# ESP32_Dongle.net
KiCad netlist of a schematic drawn in Altium Designer
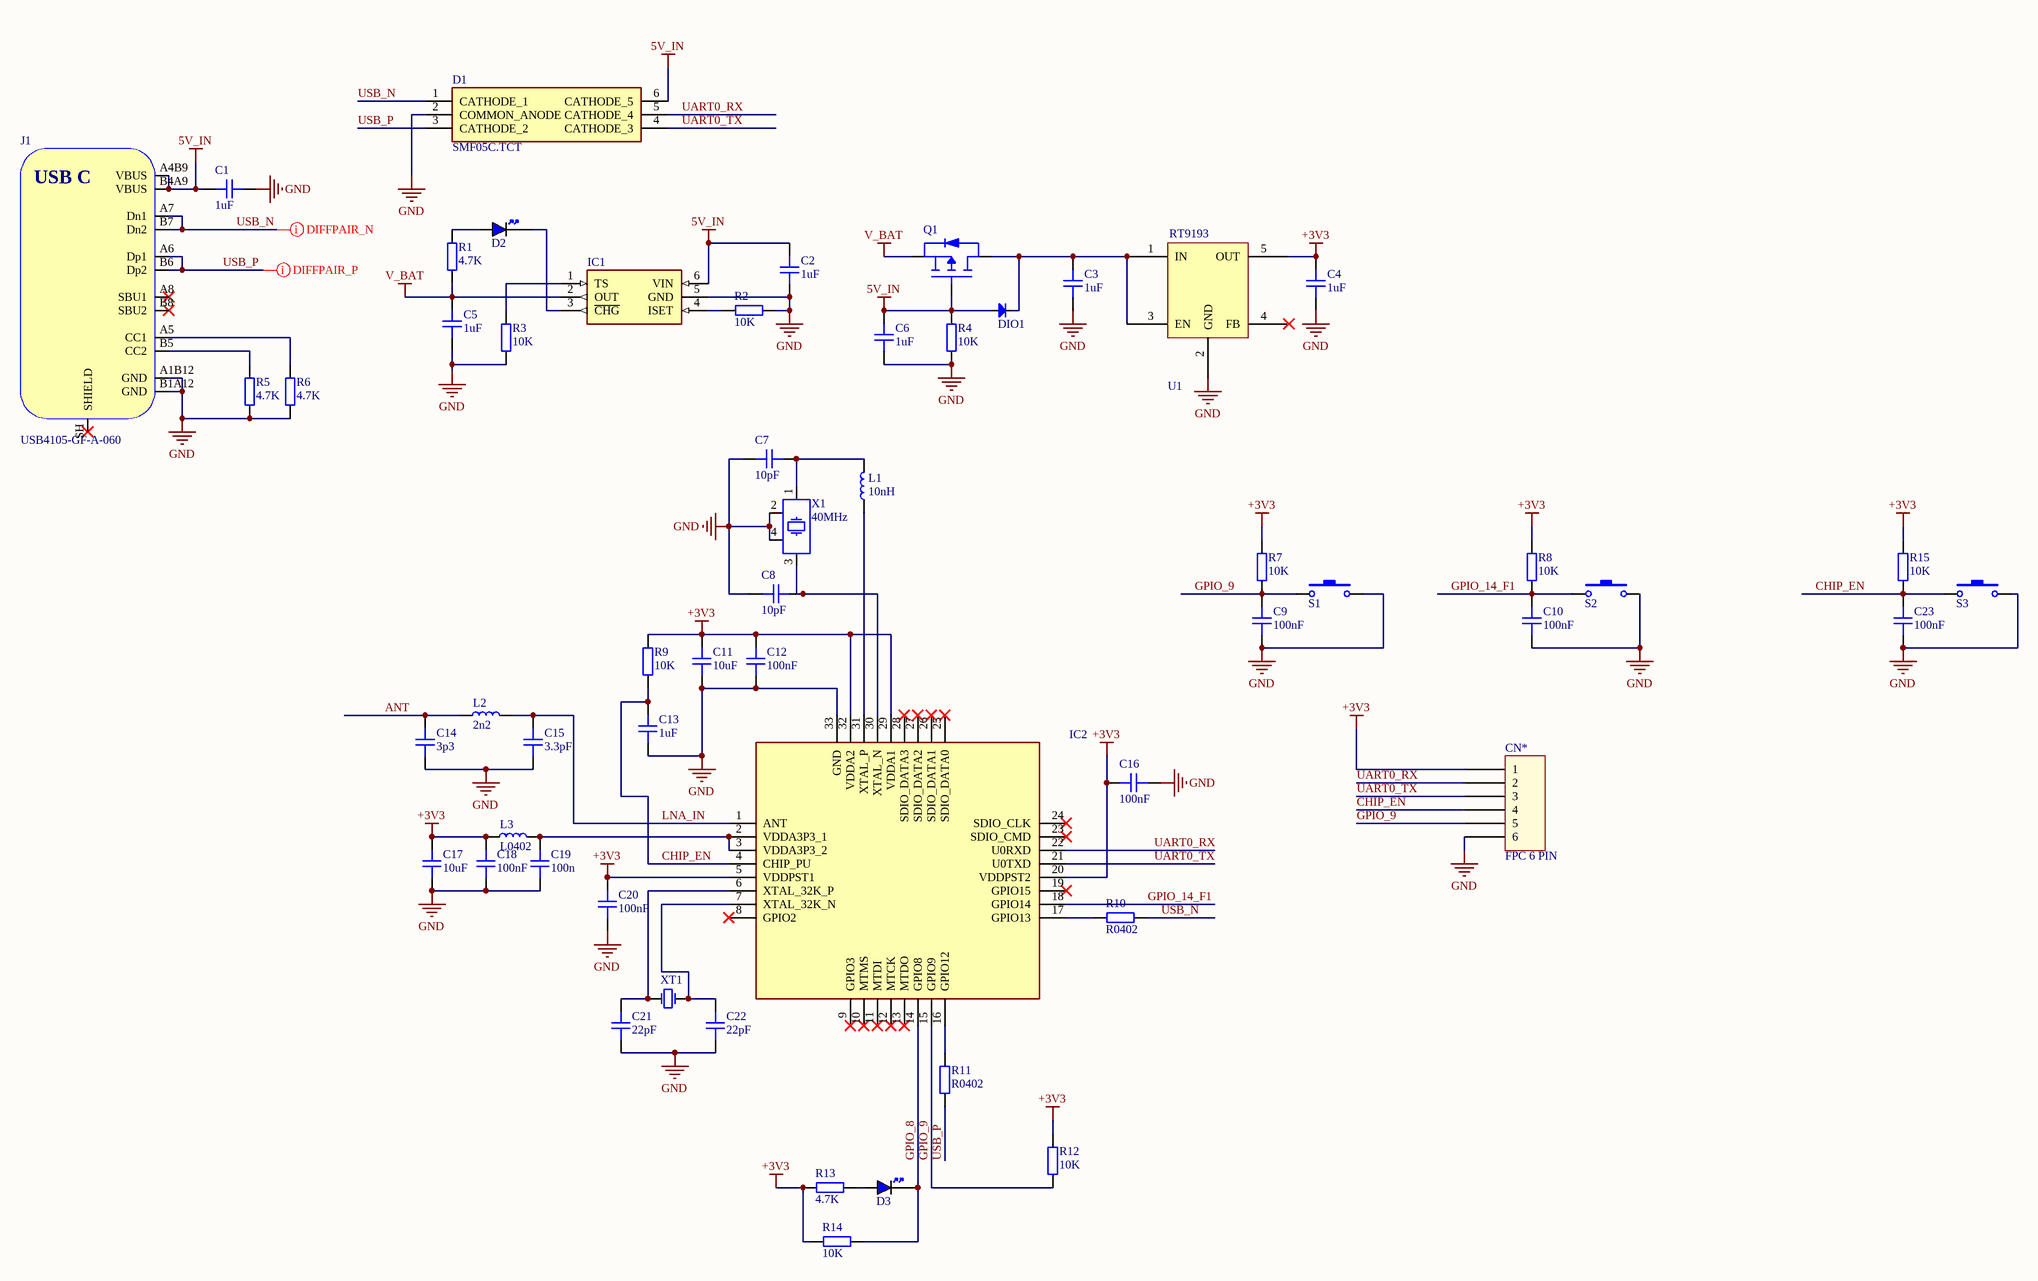
[diagram p0: ESP32_Dongle.SchDoc]

(export (version "E")
  (design (tool "Eeschema 10.0.6"))
  (components
    (comp (ref "C1")
      (value "1uF")
      (footprint "CAP_0603")
      (description "Capacitor SMD 0603 10V")
      (fields
        (field (name "MANUFACTURER") "Samsung")
        (field (name "MANUFACTURER PART NUMBER") "CL10A106KP8NNNC")
      )
      (libsource (lib "Schematic-Lib-PhilsLab") (part "CAP_0603_10V"))
    )
    (comp (ref "C2")
      (value "1uF")
      (footprint "CAP_0603")
      (description "Capacitor SMD 0603 10V")
      (fields
        (field (name "MANUFACTURER") "Samsung")
        (field (name "MANUFACTURER PART NUMBER") "CL10A106KP8NNNC")
      )
      (libsource (lib "Schematic-Lib-PhilsLab") (part "CAP_0603_10V"))
    )
    (comp (ref "C3")
      (value "1uF")
      (footprint "CAP_0603")
      (description "Capacitor SMD 0603 10V")
      (fields
        (field (name "MANUFACTURER") "Samsung")
        (field (name "MANUFACTURER PART NUMBER") "CL10A106KP8NNNC")
      )
      (libsource (lib "Schematic-Lib-PhilsLab") (part "CAP_0603_10V"))
    )
    (comp (ref "C4")
      (value "1uF")
      (footprint "CAP_0603")
      (description "Capacitor SMD 0603 10V")
      (fields
        (field (name "MANUFACTURER") "Samsung")
        (field (name "MANUFACTURER PART NUMBER") "CL10A106KP8NNNC")
      )
      (libsource (lib "Schematic-Lib-PhilsLab") (part "CAP_0603_10V"))
    )
    (comp (ref "C5")
      (value "1uF")
      (footprint "CAP_0603")
      (description "Capacitor SMD 0603 10V")
      (fields
        (field (name "MANUFACTURER") "Samsung")
        (field (name "MANUFACTURER PART NUMBER") "CL10A106KP8NNNC")
      )
      (libsource (lib "Schematic-Lib-PhilsLab") (part "CAP_0603_10V"))
    )
    (comp (ref "C6")
      (value "1uF")
      (footprint "CAP_0603")
      (description "Capacitor SMD 0603 10V")
      (fields
        (field (name "MANUFACTURER") "Samsung")
        (field (name "MANUFACTURER PART NUMBER") "CL10A106KP8NNNC")
      )
      (libsource (lib "Schematic-Lib-PhilsLab") (part "CAP_0603_10V"))
    )
    (comp (ref "C7")
      (value "10pF")
      (footprint "CAP_0402")
      (description "Capacitor SMD 0402 50V")
      (fields
        (field (name "MANUFACTURER") "Samsung")
        (field (name "MANUFACTURER PART NUMBER") "CL05C100JB5NNNC")
      )
      (libsource (lib "Schematic-Lib-PhilsLab") (part "CAP_0402_50V"))
    )
    (comp (ref "C8")
      (value "10pF")
      (footprint "CAP_0402")
      (description "Capacitor SMD 0402 50V")
      (fields
        (field (name "MANUFACTURER") "Samsung")
        (field (name "MANUFACTURER PART NUMBER") "CL05C100JB5NNNC")
      )
      (libsource (lib "Schematic-Lib-PhilsLab") (part "CAP_0402_50V"))
    )
    (comp (ref "C9")
      (value "100nF")
      (footprint "CAP_0402")
      (description "Capacitor SMD 0402 50V")
      (fields
        (field (name "MANUFACTURER") "Samsung")
        (field (name "MANUFACTURER PART NUMBER") "CL05B104KO5NNNC")
      )
      (libsource (lib "Schematic-Lib-PhilsLab") (part "CAP_0402_50V"))
    )
    (comp (ref "C10")
      (value "100nF")
      (footprint "CAP_0402")
      (description "Capacitor SMD 0402 50V")
      (fields
        (field (name "MANUFACTURER") "Samsung")
        (field (name "MANUFACTURER PART NUMBER") "CL05B104KO5NNNC")
      )
      (libsource (lib "Schematic-Lib-PhilsLab") (part "CAP_0402_50V"))
    )
    (comp (ref "C11")
      (value "10uF")
      (footprint "CAP_0603")
      (description "Capacitor SMD 0603 10V")
      (fields
        (field (name "MANUFACTURER") "Samsung")
        (field (name "MANUFACTURER PART NUMBER") "CL10A106KP8NNNC")
      )
      (libsource (lib "Schematic-Lib-PhilsLab") (part "CAP_0603_10V"))
    )
    (comp (ref "C12")
      (value "100nF")
      (footprint "CAP_0402")
      (description "Capacitor SMD 0402 50V")
      (fields
        (field (name "MANUFACTURER") "Samsung")
        (field (name "MANUFACTURER PART NUMBER") "CL05B104KO5NNNC")
      )
      (libsource (lib "Schematic-Lib-PhilsLab") (part "CAP_0402_50V"))
    )
    (comp (ref "C13")
      (value "1uF")
      (footprint "CAP_0603")
      (description "Capacitor SMD 0603 10V")
      (fields
        (field (name "MANUFACTURER") "Samsung")
        (field (name "MANUFACTURER PART NUMBER") "CL10A106KP8NNNC")
      )
      (libsource (lib "Schematic-Lib-PhilsLab") (part "CAP_0603_10V"))
    )
    (comp (ref "C14")
      (value "3p3")
      (footprint "CAP_0402")
      (description "Capacitor SMD 0402 50V")
      (fields (field (name "MANUFACTURER") "FH") (field (name "MANUFACTURER PART NUMBER") "0402CG3R3C500NT"))
      (libsource (lib "Schematic-Lib-PhilsLab") (part "CAP_0402_50V"))
    )
    (comp (ref "C15")
      (value "3.3pF")
      (footprint "CAP_0402")
      (description "Capacitor SMD 0402 50V")
      (fields (field (name "MANUFACTURER") "FH") (field (name "MANUFACTURER PART NUMBER") "0402CG3R3C500NT"))
      (libsource (lib "Schematic-Lib-PhilsLab") (part "CAP_0402_50V"))
    )
    (comp (ref "C16")
      (value "100nF")
      (footprint "CAP_0603")
      (description "Capacitor SMD 0603 10V")
      (fields
        (field (name "MANUFACTURER") "Samsung")
        (field (name "MANUFACTURER PART NUMBER") "CL10A106KP8NNNC")
      )
      (libsource (lib "Schematic-Lib-PhilsLab") (part "CAP_0603_10V"))
    )
    (comp (ref "C17")
      (value "10uF")
      (footprint "CAP_0603")
      (description "Capacitor SMD 0603 10V")
      (fields
        (field (name "MANUFACTURER") "Samsung")
        (field (name "MANUFACTURER PART NUMBER") "CL10A106KP8NNNC")
      )
      (libsource (lib "Schematic-Lib-PhilsLab") (part "CAP_0603_10V"))
    )
    (comp (ref "C18")
      (value "100nF")
      (footprint "CAP_0402")
      (description "Capacitor SMD 0402 50V")
      (fields
        (field (name "MANUFACTURER") "Samsung")
        (field (name "MANUFACTURER PART NUMBER") "CL05B104KO5NNNC")
      )
      (libsource (lib "Schematic-Lib-PhilsLab") (part "CAP_0402_50V"))
    )
    (comp (ref "C19")
      (value "100n")
      (footprint "CAP_0402")
      (description "Capacitor SMD 0402 50V")
      (fields
        (field (name "MANUFACTURER") "Samsung")
        (field (name "MANUFACTURER PART NUMBER") "CL05B104KO5NNNC")
      )
      (libsource (lib "Schematic-Lib-PhilsLab") (part "CAP_0402_50V"))
    )
    (comp (ref "C20")
      (value "100nF")
      (footprint "CAP_0603")
      (description "Capacitor SMD 0603 10V")
      (fields
        (field (name "MANUFACTURER") "Samsung")
        (field (name "MANUFACTURER PART NUMBER") "CL10A106KP8NNNC")
      )
      (libsource (lib "Schematic-Lib-PhilsLab") (part "CAP_0603_10V"))
    )
    (comp (ref "C21")
      (value "22pF")
      (footprint "CAP_0402")
      (description "Capacitor SMD 0402 50V")
      (fields
        (field (name "MANUFACTURER") "Samsung")
        (field (name "MANUFACTURER PART NUMBER") "CL05C100JB5NNNC")
      )
      (libsource (lib "Schematic-Lib-PhilsLab") (part "CAP_0402_50V"))
    )
    (comp (ref "C22")
      (value "22pF")
      (footprint "CAP_0402")
      (description "Capacitor SMD 0402 50V")
      (fields
        (field (name "MANUFACTURER") "Samsung")
        (field (name "MANUFACTURER PART NUMBER") "CL05C100JB5NNNC")
      )
      (libsource (lib "Schematic-Lib-PhilsLab") (part "CAP_0402_50V"))
    )
    (comp (ref "C23")
      (value "100nF")
      (footprint "CAP_0402")
      (description "Capacitor SMD 0402 50V")
      (fields
        (field (name "MANUFACTURER") "Samsung")
        (field (name "MANUFACTURER PART NUMBER") "CL05B104KO5NNNC")
      )
      (libsource (lib "Schematic-Lib-PhilsLab") (part "CAP_0402_50V"))
    )
    (comp (ref "CN*")
      (value "FPC 6 PIN")
      (footprint "FPC 6 PIN")
      (description "FPC 6 Pin 0.5mm")
      (libsource (lib "Digital_Isolator") (part "FPC 6 PIN"))
    )
    (comp (ref "D1")
      (value "SMF05C.TCT")
      (footprint "SM05F")
      (description "TVS Diode (Uni-directional)")
      (fields (field (name "MOUSER PART NUMBER") "947-SMF05C.TCT"))
      (libsource (lib "EZTOLOVE") (part "SMF05C.TCT"))
    )
    (comp (ref "D2")
      (value "LED_C")
      (footprint "LED_0603_BLUE")
      (description "LED 0603 BLUE SMD")
      (libsource (lib "Schematic-Lib-PhilsLab") (part "LED_0603_BLUE"))
    )
    (comp (ref "D3")
      (value "BLUE")
      (footprint "LED_0603_BLUE")
      (description "LED 0603 BLUE SMD")
      (libsource (lib "Schematic-Lib-PhilsLab") (part "LED_0603_BLUE"))
    )
    (comp (ref "DIO1")
      (value "1N4007")
      (footprint "DIO-SMD-123")
      (description "Default Diode")
      (fields (field (name "PUBLISHER") "Altium Limited"))
      (libsource (lib "My Library") (part "Diode SMD"))
    )
    (comp (ref "IC1")
      (value "BQ21040DBVR")
      (footprint "BQ21040DBVR")
      (description "Pin Charger IC")
      (fields (field (name "MOUSER PART NUMBER") "595-BQ21040DBVR"))
      (libsource (lib "Digital_Isolator") (part "BQ21040DBVR"))
    )
    (comp (ref "IC2")
      (value "ESP32-C6FH4")
      (footprint "esp32 c6FH4")
      (description "Integrated Circuit")
      (fields (field (name "MOUSER PART NUMBER") "356-ESP32-C6FH4"))
      (libsource (lib "Schematic-Lib-PhilsLab") (part "ESP32-C6FH4"))
    )
    (comp (ref "J1")
      (value "USB4105-GF-A-060")
      (footprint "USB4105-GF-A-060")
      (description "USB Connector Type C SMT 12 Pin")
      (fields (field (name "MANUFACTURER") "GCT"))
      (libsource (lib "Schematic-Lib-PhilsLab") (part "USB4105-GF-A-060"))
    )
    (comp (ref "L1")
      (value "10nH")
      (footprint "IND_0402")
      (description "Inductor SMD 0402")
      (libsource (lib "Schematic-Lib-PhilsLab") (part "IND_0402"))
    )
    (comp (ref "L2")
      (value "2n2")
      (footprint "IND_0402")
      (description "Inductor SMD 0402")
      (fields
        (field (name "MANUFACTURER") "Murata")
        (field (name "MANUFACTURER PART NUMBER") "LQW15AN2N2G80D")
      )
      (libsource (lib "") (part "IND_0402_1"))
    )
    (comp (ref "L3")
      (value "L0402")
      (footprint "IND_0402")
      (description "Inductor SMD 0402")
      (libsource (lib "Schematic-Lib-PhilsLab") (part "IND_0402"))
    )
    (comp (ref "Q1")
      (value "SSM3J338R,LF")
      (footprint "SSM3J338R,LF-SOT23-F")
      (description "MOSFET P-Channel Vds=12V Id=6A")
      (fields (field (name "MANUFACTURER PART NUMBER") "Toshiba"))
      (libsource (lib "Schematic-Lib-PhilsLab") (part "SSM3J338R,LF"))
    )
    (comp (ref "R1")
      (value "4.7K")
      (footprint "RES_0402")
      (description "Resistor SMD 0402")
      (libsource (lib "Schematic-Lib-PhilsLab") (part "RES_0402"))
    )
    (comp (ref "R2")
      (value "10K")
      (footprint "RES_0402")
      (description "Resistor SMD 0402")
      (libsource (lib "Schematic-Lib-PhilsLab") (part "RES_0402"))
    )
    (comp (ref "R3")
      (value "10K")
      (footprint "RES_0402")
      (description "Resistor SMD 0402")
      (libsource (lib "Schematic-Lib-PhilsLab") (part "RES_0402"))
    )
    (comp (ref "R4")
      (value "10K")
      (footprint "RES_0402")
      (description "Resistor SMD 0402")
      (libsource (lib "Schematic-Lib-PhilsLab") (part "RES_0402"))
    )
    (comp (ref "R5")
      (value "4.7K")
      (footprint "RES_0402")
      (description "Resistor SMD 0402")
      (libsource (lib "Schematic-Lib-PhilsLab") (part "RES_0402"))
    )
    (comp (ref "R6")
      (value "4.7K")
      (footprint "RES_0402")
      (description "Resistor SMD 0402")
      (libsource (lib "Schematic-Lib-PhilsLab") (part "RES_0402"))
    )
    (comp (ref "R7")
      (value "10K")
      (footprint "RES_0402")
      (description "Resistor SMD 0402")
      (libsource (lib "Schematic-Lib-PhilsLab") (part "RES_0402"))
    )
    (comp (ref "R8")
      (value "10K")
      (footprint "RES_0402")
      (description "Resistor SMD 0402")
      (libsource (lib "Schematic-Lib-PhilsLab") (part "RES_0402"))
    )
    (comp (ref "R9")
      (value "10K")
      (footprint "RES_0402")
      (description "Resistor SMD 0402")
      (libsource (lib "Schematic-Lib-PhilsLab") (part "RES_0402"))
    )
    (comp (ref "R10")
      (value "R0402")
      (footprint "RES_0402")
      (description "Resistor SMD 0402")
      (libsource (lib "Schematic-Lib-PhilsLab") (part "RES_0402"))
    )
    (comp (ref "R11")
      (value "R0402")
      (footprint "RES_0402")
      (description "Resistor SMD 0402")
      (libsource (lib "Schematic-Lib-PhilsLab") (part "RES_0402"))
    )
    (comp (ref "R12")
      (value "10K")
      (footprint "RES_0402")
      (description "Resistor SMD 0402")
      (libsource (lib "Schematic-Lib-PhilsLab") (part "RES_0402"))
    )
    (comp (ref "R13")
      (value "4.7K")
      (footprint "RES_0402")
      (description "Resistor SMD 0402")
      (libsource (lib "Schematic-Lib-PhilsLab") (part "RES_0402"))
    )
    (comp (ref "R14")
      (value "10K")
      (footprint "RES_0402")
      (description "Resistor SMD 0402")
      (libsource (lib "Schematic-Lib-PhilsLab") (part "RES_0402"))
    )
    (comp (ref "R15")
      (value "10K")
      (footprint "RES_0402")
      (description "Resistor SMD 0402")
      (libsource (lib "Schematic-Lib-PhilsLab") (part "RES_0402"))
    )
    (comp (ref "S1")
      (value "SW-SMD")
      (footprint "SW-SMD")
      (description "Switch")
      (fields (field (name "PUBLISHER") "Altium Limited"))
      (libsource (lib "My Library") (part "SW-SMD"))
    )
    (comp (ref "S2")
      (value "SW-SMD")
      (footprint "SW-SMD")
      (description "Switch")
      (fields (field (name "PUBLISHER") "Altium Limited"))
      (libsource (lib "My Library") (part "SW-SMD"))
    )
    (comp (ref "S3")
      (value "SW-SMD")
      (footprint "SW-SMD")
      (description "Switch")
      (fields (field (name "PUBLISHER") "Altium Limited"))
      (libsource (lib "My Library") (part "SW-SMD"))
    )
    (comp (ref "U1")
      (value "RT9193-33")
      (footprint "RT9193_33")
      (libsource (lib "EZTOLOVE") (part "RT9193-33"))
    )
    (comp (ref "X1")
      (value "40MHz")
      (footprint "XTAL_3225")
      (description "Crystal SMD 24MHz 10PPM 7pF 3225")
      (fields (field (name "MANUFACTURER") "Epson"))
      (libsource (lib "Schematic-Lib-PhilsLab") (part "TSX-3225_24.0000MF15X-AC"))
    )
    (comp (ref "XT1")
      (value "32.768KHz")
      (footprint "CRYSTAL_SMD_3.2X1.5")
      (libsource (lib "EZTOLOVE") (part "XTAL_Crystal"))
    )
  )
  (nets
    (net (code "1") (name "+3V3") (class "Default")
      (node (ref "C11") (pin "2") (pinfunction "2_2") (pintype "passive"))
      (node (ref "C12") (pin "2") (pinfunction "2_2") (pintype "passive"))
      (node (ref "C16") (pin "2") (pinfunction "2_2") (pintype "passive"))
      (node (ref "C17") (pin "2") (pinfunction "2_2") (pintype "passive"))
      (node (ref "C18") (pin "2") (pinfunction "2_2") (pintype "passive"))
      (node (ref "C20") (pin "2") (pinfunction "2_2") (pintype "passive"))
      (node (ref "C4") (pin "1") (pinfunction "1_1") (pintype "passive"))
      (node (ref "CN*") (pin "1") (pinfunction "1_1") (pintype "passive"))
      (node (ref "IC2") (pin "20") (pinfunction "VDDPST2_20") (pintype "passive"))
      (node (ref "IC2") (pin "29") (pinfunction "VDDA1_29") (pintype "passive"))
      (node (ref "IC2") (pin "32") (pinfunction "VDDA2_32") (pintype "passive"))
      (node (ref "IC2") (pin "5") (pinfunction "VDDPST1_5") (pintype "passive"))
      (node (ref "L3") (pin "1") (pinfunction "1_1") (pintype "passive"))
      (node (ref "R12") (pin "2") (pinfunction "2_2") (pintype "passive"))
      (node (ref "R13") (pin "1") (pinfunction "1_1") (pintype "passive"))
      (node (ref "R14") (pin "1") (pinfunction "1_1") (pintype "passive"))
      (node (ref "R15") (pin "2") (pinfunction "2_2") (pintype "passive"))
      (node (ref "R7") (pin "2") (pinfunction "2_2") (pintype "passive"))
      (node (ref "R8") (pin "2") (pinfunction "2_2") (pintype "passive"))
      (node (ref "R9") (pin "2") (pinfunction "2_2") (pintype "passive"))
      (node (ref "U1") (pin "5") (pinfunction "OUT_5") (pintype "passive"))
    )
    (net (code "2") (name "/ANT") (class "Default")
      (node (ref "C14") (pin "2") (pinfunction "2_2") (pintype "passive"))
      (node (ref "L2") (pin "2") (pinfunction "2_2") (pintype "passive"))
    )
    (net (code "3") (name "/CHIP_EN") (class "Default")
      (node (ref "C13") (pin "2") (pinfunction "2_2") (pintype "passive"))
      (node (ref "C23") (pin "2") (pinfunction "2_2") (pintype "passive"))
      (node (ref "CN*") (pin "4") (pinfunction "4_4") (pintype "passive"))
      (node (ref "IC2") (pin "4") (pinfunction "CHIP_PU_4") (pintype "passive"))
      (node (ref "R15") (pin "1") (pinfunction "1_1") (pintype "passive"))
      (node (ref "R9") (pin "1") (pinfunction "1_1") (pintype "passive"))
      (node (ref "S3") (pin "1") (pinfunction "1_1") (pintype "passive"))
    )
    (net (code "4") (name "/GPIO_8") (class "Default")
      (node (ref "D3") (pin "K") (pinfunction "K_K") (pintype "passive"))
      (node (ref "IC2") (pin "14") (pinfunction "GPIO8_14") (pintype "passive"))
      (node (ref "R14") (pin "2") (pinfunction "2_2") (pintype "passive"))
    )
    (net (code "5") (name "/GPIO_9") (class "Default")
      (node (ref "C9") (pin "2") (pinfunction "2_2") (pintype "passive"))
      (node (ref "CN*") (pin "5") (pinfunction "5_5") (pintype "passive"))
      (node (ref "IC2") (pin "15") (pinfunction "GPIO9_15") (pintype "passive"))
      (node (ref "R12") (pin "1") (pinfunction "1_1") (pintype "passive"))
      (node (ref "R7") (pin "1") (pinfunction "1_1") (pintype "passive"))
      (node (ref "S1") (pin "1") (pinfunction "1_1") (pintype "passive"))
    )
    (net (code "6") (name "/GPIO_14_F1") (class "Default")
      (node (ref "C10") (pin "2") (pinfunction "2_2") (pintype "passive"))
      (node (ref "IC2") (pin "18") (pinfunction "GPIO14_18") (pintype "passive"))
      (node (ref "R8") (pin "1") (pinfunction "1_1") (pintype "passive"))
      (node (ref "S2") (pin "1") (pinfunction "1_1") (pintype "passive"))
    )
    (net (code "7") (name "/LNA_IN") (class "Default")
      (node (ref "C15") (pin "2") (pinfunction "2_2") (pintype "passive"))
      (node (ref "IC2") (pin "1") (pinfunction "ANT_1") (pintype "passive"))
      (node (ref "L2") (pin "1") (pinfunction "1_1") (pintype "passive"))
    )
    (net (code "8") (name "/UART0_RX") (class "Default")
      (node (ref "CN*") (pin "2") (pinfunction "2_2") (pintype "passive"))
      (node (ref "D1") (pin "5") (pinfunction "CATHODE_4_5") (pintype "passive"))
      (node (ref "IC2") (pin "22") (pinfunction "U0RXD_22") (pintype "passive"))
    )
    (net (code "9") (name "/UART0_TX") (class "Default")
      (node (ref "CN*") (pin "3") (pinfunction "3_3") (pintype "passive"))
      (node (ref "D1") (pin "4") (pinfunction "CATHODE_3_4") (pintype "passive"))
      (node (ref "IC2") (pin "21") (pinfunction "U0TXD_21") (pintype "passive"))
    )
    (net (code "10") (name "/USB_N") (class "Default")
      (node (ref "D1") (pin "1") (pinfunction "CATHODE_1_1") (pintype "passive"))
      (node (ref "J1") (pin "A7") (pinfunction "Dn1_A7") (pintype "passive"))
      (node (ref "J1") (pin "B7") (pinfunction "Dn2_B7") (pintype "passive"))
      (node (ref "R10") (pin "2") (pinfunction "2_2") (pintype "passive"))
    )
    (net (code "11") (name "/USB_P") (class "Default")
      (node (ref "D1") (pin "3") (pinfunction "CATHODE_2_3") (pintype "passive"))
      (node (ref "J1") (pin "A6") (pinfunction "Dp1_A6") (pintype "passive"))
      (node (ref "J1") (pin "B6") (pinfunction "Dp2_B6") (pintype "passive"))
      (node (ref "R11") (pin "1") (pinfunction "1_1") (pintype "passive"))
    )
    (net (code "12") (name "5V_IN") (class "Default")
      (node (ref "C1") (pin "1") (pinfunction "1_1") (pintype "passive"))
      (node (ref "C2") (pin "1") (pinfunction "1_1") (pintype "passive"))
      (node (ref "C6") (pin "1") (pinfunction "1_1") (pintype "passive"))
      (node (ref "D1") (pin "6") (pinfunction "CATHODE_5_6") (pintype "passive"))
      (node (ref "DIO1") (pin "1") (pinfunction "A_1") (pintype "passive"))
      (node (ref "IC1") (pin "6") (pinfunction "VIN_6") (pintype "input"))
      (node (ref "J1") (pin "A4B9") (pinfunction "VBUS_A4B9") (pintype "passive"))
      (node (ref "J1") (pin "B4A9") (pinfunction "VBUS_B4A9") (pintype "passive"))
      (node (ref "Q1") (pin "G") (pinfunction "G_G") (pintype "passive"))
      (node (ref "R4") (pin "2") (pinfunction "2_2") (pintype "passive"))
    )
    (net (code "13") (name "GND") (class "Default")
      (node (ref "C1") (pin "2") (pinfunction "2_2") (pintype "passive"))
      (node (ref "C10") (pin "1") (pinfunction "1_1") (pintype "passive"))
      (node (ref "C11") (pin "1") (pinfunction "1_1") (pintype "passive"))
      (node (ref "C12") (pin "1") (pinfunction "1_1") (pintype "passive"))
      (node (ref "C13") (pin "1") (pinfunction "1_1") (pintype "passive"))
      (node (ref "C14") (pin "1") (pinfunction "1_1") (pintype "passive"))
      (node (ref "C15") (pin "1") (pinfunction "1_1") (pintype "passive"))
      (node (ref "C16") (pin "1") (pinfunction "1_1") (pintype "passive"))
      (node (ref "C17") (pin "1") (pinfunction "1_1") (pintype "passive"))
      (node (ref "C18") (pin "1") (pinfunction "1_1") (pintype "passive"))
      (node (ref "C19") (pin "1") (pinfunction "1_1") (pintype "passive"))
      (node (ref "C2") (pin "2") (pinfunction "2_2") (pintype "passive"))
      (node (ref "C20") (pin "1") (pinfunction "1_1") (pintype "passive"))
      (node (ref "C21") (pin "2") (pinfunction "2_2") (pintype "passive"))
      (node (ref "C22") (pin "2") (pinfunction "2_2") (pintype "passive"))
      (node (ref "C23") (pin "1") (pinfunction "1_1") (pintype "passive"))
      (node (ref "C3") (pin "2") (pinfunction "2_2") (pintype "passive"))
      (node (ref "C4") (pin "2") (pinfunction "2_2") (pintype "passive"))
      (node (ref "C5") (pin "2") (pinfunction "2_2") (pintype "passive"))
      (node (ref "C6") (pin "2") (pinfunction "2_2") (pintype "passive"))
      (node (ref "C7") (pin "2") (pinfunction "2_2") (pintype "passive"))
      (node (ref "C8") (pin "2") (pinfunction "2_2") (pintype "passive"))
      (node (ref "C9") (pin "1") (pinfunction "1_1") (pintype "passive"))
      (node (ref "CN*") (pin "6") (pinfunction "6_6") (pintype "passive"))
      (node (ref "D1") (pin "2") (pinfunction "COMMON_ANODE_2") (pintype "passive"))
      (node (ref "IC1") (pin "5") (pinfunction "GND_5") (pintype "power_in"))
      (node (ref "IC2") (pin "33") (pinfunction "GND_33") (pintype "passive"))
      (node (ref "J1") (pin "A1B12") (pinfunction "GND_A1B12") (pintype "passive"))
      (node (ref "J1") (pin "B1A12") (pinfunction "GND_B1A12") (pintype "passive"))
      (node (ref "R2") (pin "2") (pinfunction "2_2") (pintype "passive"))
      (node (ref "R3") (pin "2") (pinfunction "2_2") (pintype "passive"))
      (node (ref "R4") (pin "1") (pinfunction "1_1") (pintype "passive"))
      (node (ref "R5") (pin "1") (pinfunction "1_1") (pintype "passive"))
      (node (ref "R6") (pin "1") (pinfunction "1_1") (pintype "passive"))
      (node (ref "S1") (pin "2") (pinfunction "2_2") (pintype "passive"))
      (node (ref "S2") (pin "2") (pinfunction "2_2") (pintype "passive"))
      (node (ref "S3") (pin "2") (pinfunction "2_2") (pintype "passive"))
      (node (ref "U1") (pin "2") (pinfunction "GND_2") (pintype "passive"))
      (node (ref "X1") (pin "2") (pinfunction "2_2") (pintype "passive"))
      (node (ref "X1") (pin "4") (pinfunction "4_4") (pintype "passive"))
    )
    (net (code "14") (name "Net-(C7-Pad1)") (class "Default")
      (node (ref "C7") (pin "1") (pinfunction "1_1") (pintype "passive"))
      (node (ref "L1") (pin "2") (pinfunction "2_2") (pintype "passive"))
      (node (ref "X1") (pin "1") (pinfunction "1_1") (pintype "passive"))
    )
    (net (code "15") (name "Net-(D2-PadA)") (class "Default")
      (node (ref "D2") (pin "A") (pinfunction "A_A") (pintype "passive"))
      (node (ref "R1") (pin "2") (pinfunction "2_2") (pintype "passive"))
    )
    (net (code "16") (name "Net-(D3-PadA)") (class "Default")
      (node (ref "D3") (pin "A") (pinfunction "A_A") (pintype "passive"))
      (node (ref "R13") (pin "2") (pinfunction "2_2") (pintype "passive"))
    )
    (net (code "17") (name "Net-(DIO1-K)") (class "Default")
      (node (ref "C3") (pin "1") (pinfunction "1_1") (pintype "passive"))
      (node (ref "DIO1") (pin "2") (pinfunction "K_2") (pintype "passive"))
      (node (ref "Q1") (pin "D") (pinfunction "D_D") (pintype "passive"))
      (node (ref "U1") (pin "1") (pinfunction "IN_1") (pintype "passive"))
      (node (ref "U1") (pin "3") (pinfunction "EN_3") (pintype "passive"))
    )
    (net (code "18") (name "Net-(IC1-ISET)") (class "Default")
      (node (ref "IC1") (pin "4") (pinfunction "ISET_4") (pintype "input"))
      (node (ref "R2") (pin "1") (pinfunction "1_1") (pintype "passive"))
    )
    (net (code "19") (name "Net-(IC1-TS)") (class "Default")
      (node (ref "IC1") (pin "1") (pinfunction "TS_1") (pintype "input"))
      (node (ref "R3") (pin "1") (pinfunction "1_1") (pintype "passive"))
    )
    (net (code "20") (name "Net-(IC1-~{CHG})") (class "Default")
      (node (ref "D2") (pin "K") (pinfunction "K_K") (pintype "passive"))
      (node (ref "IC1") (pin "3") (pinfunction "~{CHG}_3") (pintype "output"))
    )
    (net (code "21") (name "Net-(IC2-GPIO12)") (class "Default")
      (node (ref "IC2") (pin "16") (pinfunction "GPIO12_16") (pintype "passive"))
      (node (ref "R11") (pin "2") (pinfunction "2_2") (pintype "passive"))
    )
    (net (code "22") (name "Net-(IC2-GPIO13)") (class "Default")
      (node (ref "IC2") (pin "17") (pinfunction "GPIO13_17") (pintype "passive"))
      (node (ref "R10") (pin "1") (pinfunction "1_1") (pintype "passive"))
    )
    (net (code "23") (name "Net-(IC2-VDDA3P3_1)") (class "Default")
      (node (ref "C19") (pin "2") (pinfunction "2_2") (pintype "passive"))
      (node (ref "IC2") (pin "2") (pinfunction "VDDA3P3_1_2") (pintype "passive"))
      (node (ref "IC2") (pin "3") (pinfunction "VDDA3P3_2_3") (pintype "passive"))
      (node (ref "L3") (pin "2") (pinfunction "2_2") (pintype "passive"))
    )
    (net (code "24") (name "Net-(IC2-XTAL_32K_N)") (class "Default")
      (node (ref "C22") (pin "1") (pinfunction "1_1") (pintype "passive"))
      (node (ref "IC2") (pin "7") (pinfunction "XTAL_32K_N_7") (pintype "passive"))
      (node (ref "XT1") (pin "2") (pinfunction "OSC2_2") (pintype "passive"))
    )
    (net (code "25") (name "Net-(IC2-XTAL_32K_P)") (class "Default")
      (node (ref "C21") (pin "1") (pinfunction "1_1") (pintype "passive"))
      (node (ref "IC2") (pin "6") (pinfunction "XTAL_32K_P_6") (pintype "passive"))
      (node (ref "XT1") (pin "1") (pinfunction "OSC1_1") (pintype "passive"))
    )
    (net (code "26") (name "Net-(IC2-XTAL_N)") (class "Default")
      (node (ref "C8") (pin "1") (pinfunction "1_1") (pintype "passive"))
      (node (ref "IC2") (pin "30") (pinfunction "XTAL_N_30") (pintype "passive"))
      (node (ref "X1") (pin "3") (pinfunction "3_3") (pintype "passive"))
    )
    (net (code "27") (name "Net-(IC2-XTAL_P)") (class "Default")
      (node (ref "IC2") (pin "31") (pinfunction "XTAL_P_31") (pintype "passive"))
      (node (ref "L1") (pin "1") (pinfunction "1_1") (pintype "passive"))
    )
    (net (code "28") (name "Net-(J1-CC1)") (class "Default")
      (node (ref "J1") (pin "A5") (pinfunction "CC1_A5") (pintype "passive"))
      (node (ref "R6") (pin "2") (pinfunction "2_2") (pintype "passive"))
    )
    (net (code "29") (name "Net-(J1-CC2)") (class "Default")
      (node (ref "J1") (pin "B5") (pinfunction "CC2_B5") (pintype "passive"))
      (node (ref "R5") (pin "2") (pinfunction "2_2") (pintype "passive"))
    )
    (net (code "30") (name "V_BAT") (class "Default")
      (node (ref "C5") (pin "1") (pinfunction "1_1") (pintype "passive"))
      (node (ref "IC1") (pin "2") (pinfunction "OUT_2") (pintype "output"))
      (node (ref "Q1") (pin "S") (pinfunction "S_S") (pintype "passive"))
      (node (ref "R1") (pin "1") (pinfunction "1_1") (pintype "passive"))
    )
    (net (code "31") (name "unconnected-(IC2-GPIO2-Pad8)") (class "Default")
      (node (ref "IC2") (pin "8") (pinfunction "GPIO2_8") (pintype "passive+no_connect"))
    )
    (net (code "32") (name "unconnected-(IC2-GPIO3-Pad9)") (class "Default")
      (node (ref "IC2") (pin "9") (pinfunction "GPIO3_9") (pintype "passive+no_connect"))
    )
    (net (code "33") (name "unconnected-(IC2-GPIO15-Pad19)") (class "Default")
      (node (ref "IC2") (pin "19") (pinfunction "GPIO15_19") (pintype "passive+no_connect"))
    )
    (net (code "34") (name "unconnected-(IC2-MTCK-Pad12)") (class "Default")
      (node (ref "IC2") (pin "12") (pinfunction "MTCK_12") (pintype "passive+no_connect"))
    )
    (net (code "35") (name "unconnected-(IC2-MTDI-Pad11)") (class "Default")
      (node (ref "IC2") (pin "11") (pinfunction "MTDI_11") (pintype "passive+no_connect"))
    )
    (net (code "36") (name "unconnected-(IC2-MTDO-Pad13)") (class "Default")
      (node (ref "IC2") (pin "13") (pinfunction "MTDO_13") (pintype "passive+no_connect"))
    )
    (net (code "37") (name "unconnected-(IC2-MTMS-Pad10)") (class "Default")
      (node (ref "IC2") (pin "10") (pinfunction "MTMS_10") (pintype "passive+no_connect"))
    )
    (net (code "38") (name "unconnected-(IC2-SDIO_CLK-Pad24)") (class "Default")
      (node (ref "IC2") (pin "24") (pinfunction "SDIO_CLK_24") (pintype "passive+no_connect"))
    )
    (net (code "39") (name "unconnected-(IC2-SDIO_CMD-Pad23)") (class "Default")
      (node (ref "IC2") (pin "23") (pinfunction "SDIO_CMD_23") (pintype "passive+no_connect"))
    )
    (net (code "40") (name "unconnected-(IC2-SDIO_DATA0-Pad25)") (class "Default")
      (node (ref "IC2") (pin "25") (pinfunction "SDIO_DATA0_25") (pintype "passive+no_connect"))
    )
    (net (code "41") (name "unconnected-(IC2-SDIO_DATA1-Pad26)") (class "Default")
      (node (ref "IC2") (pin "26") (pinfunction "SDIO_DATA1_26") (pintype "passive+no_connect"))
    )
    (net (code "42") (name "unconnected-(IC2-SDIO_DATA2-Pad27)") (class "Default")
      (node (ref "IC2") (pin "27") (pinfunction "SDIO_DATA2_27") (pintype "passive+no_connect"))
    )
    (net (code "43") (name "unconnected-(IC2-SDIO_DATA3-Pad28)") (class "Default")
      (node (ref "IC2") (pin "28") (pinfunction "SDIO_DATA3_28") (pintype "passive+no_connect"))
    )
    (net (code "44") (name "unconnected-(J1-SBU1-PadA8)") (class "Default")
      (node (ref "J1") (pin "A8") (pinfunction "SBU1_A8") (pintype "passive+no_connect"))
    )
    (net (code "45") (name "unconnected-(J1-SBU2-PadB8)") (class "Default")
      (node (ref "J1") (pin "B8") (pinfunction "SBU2_B8") (pintype "passive+no_connect"))
    )
    (net (code "46") (name "unconnected-(J1-SHIELD-PadSH)") (class "Default")
      (node (ref "J1") (pin "SH") (pinfunction "SHIELD_SH") (pintype "passive+no_connect"))
    )
    (net (code "47") (name "unconnected-(U1-FB-Pad4)") (class "Default")
      (node (ref "U1") (pin "4") (pinfunction "FB_4") (pintype "passive+no_connect"))
    )
  )
)
